# Clk.net
KiCad netlist of a schematic drawn in Altium Designer
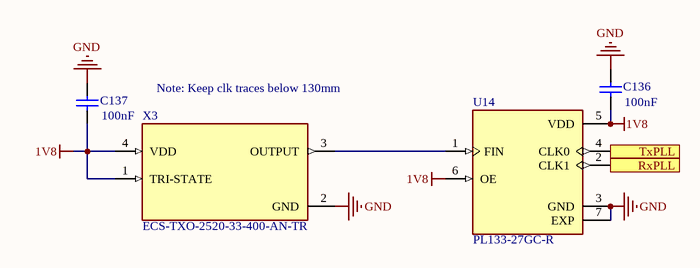
[diagram p0: Clk.SchDoc]

(export (version "E")
  (design (tool "Eeschema 10.0.6"))
  (components
    (comp (ref "C136")
      (value "100nF")
      (footprint "0402-A")
      (description "Capacitor")
      (fields (field (name "Comment") "Cap") (field (name "PUBLISHER") "Altium Limited"))
      (libsource (lib "Miscellaneous Devices") (part "Cap"))
    )
    (comp (ref "C137")
      (value "100nF")
      (footprint "0402-A")
      (description "Capacitor")
      (fields (field (name "Comment") "Cap") (field (name "PUBLISHER") "Altium Limited"))
      (libsource (lib "Miscellaneous Devices") (part "Cap"))
    )
    (comp (ref "U14")
      (value "PL133-27GC-R")
      (footprint "SON40P130X200X60-7N")
      (description "Clock Fanout Buffer _Distribution_ IC 1:2 150MHz 6-UFDFN Exposed Pad")
      (fields (field (name "MF") "Microchip"))
      (libsource (lib "PL133-27GC-R") (part "PL133-27GC-R"))
    )
    (comp (ref "X3")
      (value "ECS-TXO-2520-33-400-AN-TR")
      (footprint "OSC_ECS-TXO-2520-33-400-AN-TR")
      (description "40MHz TCXO HCMOS Oscillator 3.3V Enable/Disable 4-SMD, No Lead")
      (fields (field (name "MF") "ECS Inc."))
      (libsource (lib "ECS-TXO-2520-33-400-AN-TR") (part "ECS-TXO-2520-33-400-AN-TR"))
    )
  )
  (nets
    (net (code "1") (name "/RxPLL") (class "Default")
      (node (ref "U14") (pin "2") (pinfunction "CLK1_2") (pintype "output"))
    )
    (net (code "2") (name "/TxPLL") (class "Default")
      (node (ref "U14") (pin "4") (pinfunction "CLK0_4") (pintype "output"))
    )
    (net (code "3") (name "1V8") (class "Default")
      (node (ref "C136") (pin "2") (pinfunction "2_2") (pintype "passive"))
      (node (ref "C137") (pin "2") (pinfunction "2_2") (pintype "passive"))
      (node (ref "U14") (pin "5") (pinfunction "VDD_5") (pintype "power_in"))
      (node (ref "U14") (pin "6") (pinfunction "OE_6") (pintype "input"))
      (node (ref "X3") (pin "1") (pinfunction "TRI-STATE_1") (pintype "input"))
      (node (ref "X3") (pin "4") (pinfunction "VDD_4") (pintype "input"))
    )
    (net (code "4") (name "GND") (class "Default")
      (node (ref "C136") (pin "1") (pinfunction "1_1") (pintype "passive"))
      (node (ref "C137") (pin "1") (pinfunction "1_1") (pintype "passive"))
      (node (ref "U14") (pin "3") (pinfunction "GND_3") (pintype "power_in"))
      (node (ref "U14") (pin "7") (pinfunction "EXP_7") (pintype "power_in"))
      (node (ref "X3") (pin "2") (pinfunction "GND_2") (pintype "power_in"))
    )
    (net (code "5") (name "Net-(U14-FIN)") (class "Default")
      (node (ref "U14") (pin "1") (pinfunction "FIN_1") (pintype "input"))
      (node (ref "X3") (pin "3") (pinfunction "OUTPUT_3") (pintype "output"))
    )
  )
)
